# 795506519DJFLY-DG.net
KiCad netlist of a schematic drawn in Altium Designer
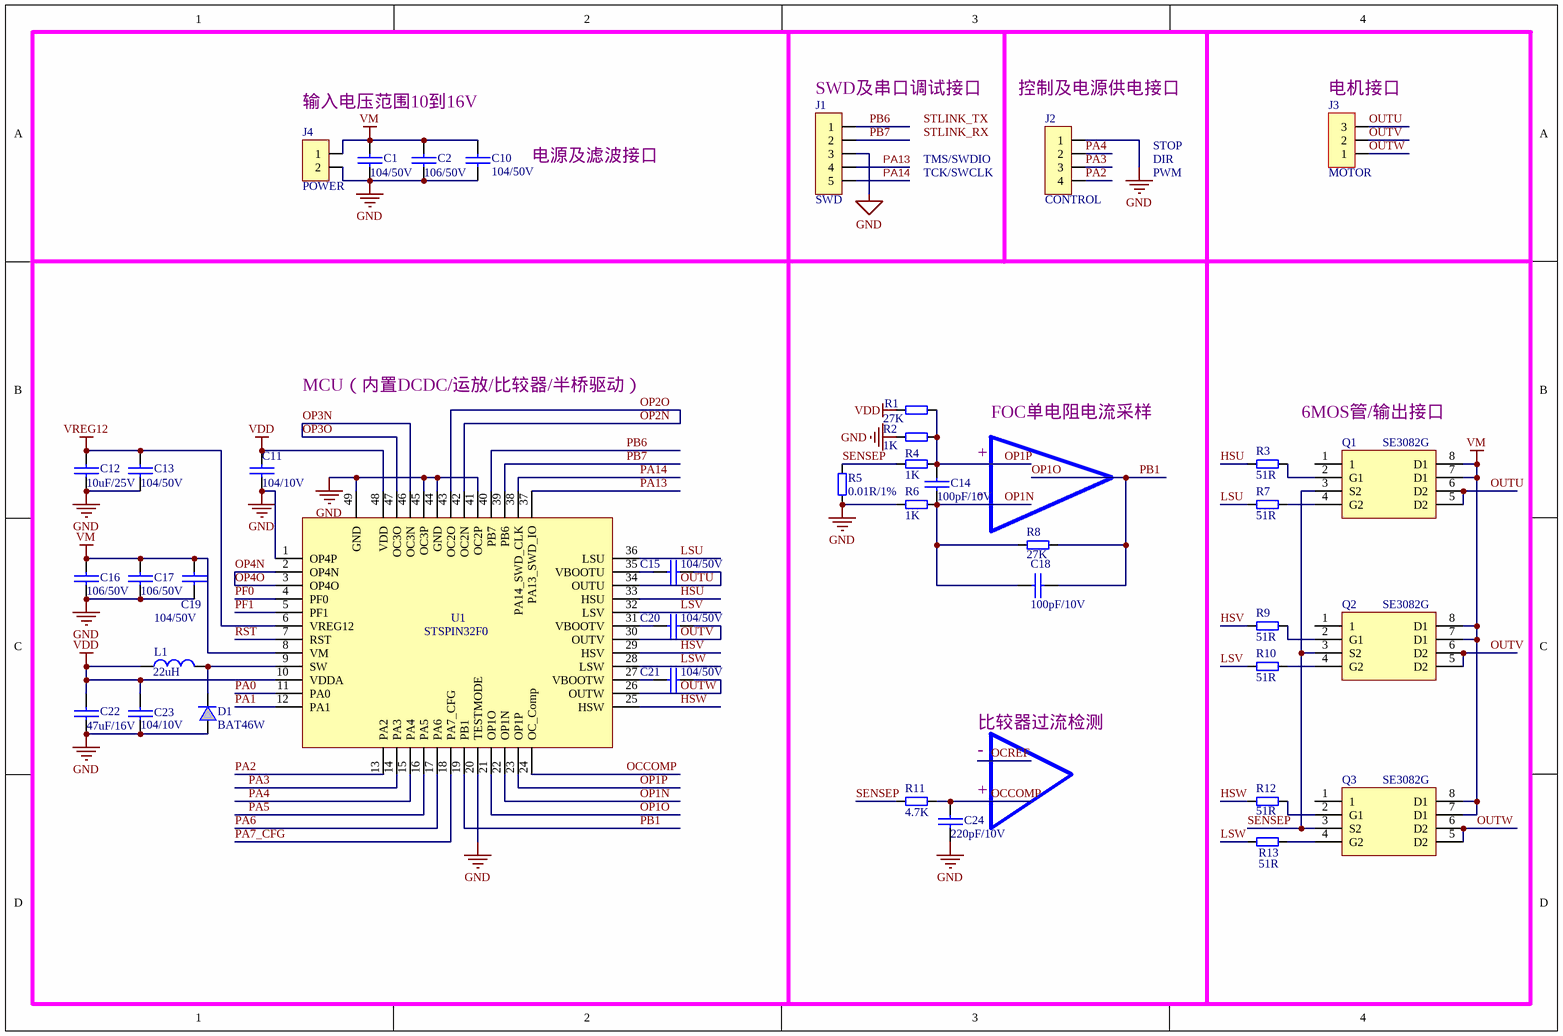
[diagram p0: 795506519DJFLY-DG.SchDoc]

(export (version "E")
  (design (tool "Eeschema 10.0.6"))
  (components
    (comp (ref "C1")
      (value "104/50V")
      (footprint "0805C")
      (description "C")
      (libsource (lib "zh") (part "C"))
    )
    (comp (ref "C2")
      (value "106/50V")
      (footprint "1206C")
      (description "C")
      (libsource (lib "zh") (part "C"))
    )
    (comp (ref "C10")
      (value "104/50V")
      (footprint "0805C")
      (description "C")
      (libsource (lib "zh") (part "C"))
    )
    (comp (ref "C11")
      (value "104/10V")
      (footprint "0603C")
      (description "C")
      (libsource (lib "zh") (part "C"))
    )
    (comp (ref "C12")
      (value "10uF/25V")
      (footprint "1206C")
      (description "C")
      (libsource (lib "zh") (part "C"))
    )
    (comp (ref "C13")
      (value "104/50V")
      (footprint "0805C")
      (description "C")
      (libsource (lib "zh") (part "C"))
    )
    (comp (ref "C14")
      (value "100pF/10V")
      (footprint "0603C")
      (description "C")
      (libsource (lib "zh") (part "C"))
    )
    (comp (ref "C15")
      (value "104/50V")
      (footprint "0805C")
      (description "C")
      (libsource (lib "zh") (part "C"))
    )
    (comp (ref "C16")
      (value "106/50V")
      (footprint "1206C")
      (description "C")
      (libsource (lib "zh") (part "C"))
    )
    (comp (ref "C17")
      (value "106/50V")
      (footprint "1206C")
      (description "C")
      (libsource (lib "zh") (part "C"))
    )
    (comp (ref "C18")
      (value "100pF/10V")
      (footprint "0603C")
      (description "C")
      (libsource (lib "zh") (part "C"))
    )
    (comp (ref "C19")
      (value "104/50V")
      (footprint "0805C")
      (description "C")
      (libsource (lib "zh") (part "C"))
    )
    (comp (ref "C20")
      (value "104/50V")
      (footprint "0805C")
      (description "C")
      (libsource (lib "zh") (part "C"))
    )
    (comp (ref "C21")
      (value "104/50V")
      (footprint "0805C")
      (description "C")
      (libsource (lib "zh") (part "C"))
    )
    (comp (ref "C22")
      (value "47uF/16V")
      (footprint "1206C")
      (description "C")
      (libsource (lib "zh") (part "C"))
    )
    (comp (ref "C23")
      (value "104/10V")
      (footprint "0603C")
      (description "C")
      (libsource (lib "zh") (part "C"))
    )
    (comp (ref "C24")
      (value "220pF/10V")
      (footprint "0603C")
      (description "C")
      (libsource (lib "zh") (part "C"))
    )
    (comp (ref "D1")
      (value "BAT46W")
      (footprint "SOD-123")
      (description "D")
      (libsource (lib "zh") (part "D"))
    )
    (comp (ref "J1") (value "SWD") (footprint "SIP5") (description "CN") (libsource (lib "zh") (part "CON5")))
    (comp (ref "J2")
      (value "CONTROL")
      (footprint "SIP4")
      (description "CN")
      (libsource (lib "zh") (part "CON4"))
    )
    (comp (ref "J3")
      (value "MOTOR")
      (footprint "POW-3.81-3S")
      (description "CN")
      (libsource (lib "zh") (part "CON3"))
    )
    (comp (ref "J4")
      (value "POWER")
      (footprint "POW-3.81-2S")
      (description "J")
      (libsource (lib "zh") (part "CON2"))
    )
    (comp (ref "L1")
      (value "22uH")
      (footprint "1812c")
      (description "10uH")
      (libsource (lib "zh1") (part "L"))
    )
    (comp (ref "Q1") (value "SE3082G") (footprint "DFN5*6") (libsource (lib "LY-SCH") (part "SE3082G")))
    (comp (ref "Q2") (value "SE3082G") (footprint "DFN5*6") (libsource (lib "LY-SCH") (part "SE3082G")))
    (comp (ref "Q3") (value "SE3082G") (footprint "DFN5*6") (libsource (lib "LY-SCH") (part "SE3082G")))
    (comp (ref "R1") (value "27K") (footprint "0603") (description "10K") (libsource (lib "zh") (part "R")))
    (comp (ref "R2") (value "1K") (footprint "0603") (description "10K") (libsource (lib "zh") (part "R")))
    (comp (ref "R3") (value "51R") (footprint "0805") (description "10K") (libsource (lib "zh1") (part "R")))
    (comp (ref "R4") (value "1K") (footprint "0603") (description "10K") (libsource (lib "zh") (part "R")))
    (comp (ref "R5")
      (value "0.01R/1%")
      (footprint "2512-K")
      (description "10K")
      (libsource (lib "zh") (part "R"))
    )
    (comp (ref "R6") (value "1K") (footprint "0603") (description "10K") (libsource (lib "zh") (part "R")))
    (comp (ref "R7") (value "51R") (footprint "0805") (description "10K") (libsource (lib "zh1") (part "R")))
    (comp (ref "R8") (value "27K") (footprint "0603") (description "10K") (libsource (lib "zh") (part "R")))
    (comp (ref "R9") (value "51R") (footprint "0805") (description "10K") (libsource (lib "zh1") (part "R")))
    (comp (ref "R10") (value "51R") (footprint "0805") (description "10K") (libsource (lib "zh1") (part "R")))
    (comp (ref "R11") (value "4.7K") (footprint "0603") (description "10K") (libsource (lib "zh") (part "R")))
    (comp (ref "R12") (value "51R") (footprint "0805") (description "10K") (libsource (lib "zh1") (part "R")))
    (comp (ref "R13") (value "51R") (footprint "0805") (description "10K") (libsource (lib "zh1") (part "R")))
    (comp (ref "U1")
      (value "STSPIN32F0")
      (footprint "VFQFPN48")
      (libsource (lib "LY-SCH") (part "STSPIN32F0"))
    )
  )
  (nets
    (net (code "1") (name "/HSU") (class "Default")
      (node (ref "R3") (pin "1") (pinfunction "1_1") (pintype "passive"))
      (node (ref "U1") (pin "33") (pinfunction "HSU_33") (pintype "passive"))
    )
    (net (code "2") (name "/HSV") (class "Default")
      (node (ref "R9") (pin "1") (pinfunction "1_1") (pintype "passive"))
      (node (ref "U1") (pin "29") (pinfunction "HSV_29") (pintype "passive"))
    )
    (net (code "3") (name "/HSW") (class "Default")
      (node (ref "R12") (pin "1") (pinfunction "1_1") (pintype "passive"))
      (node (ref "U1") (pin "25") (pinfunction "HSW_25") (pintype "passive"))
    )
    (net (code "4") (name "/LSU") (class "Default")
      (node (ref "R7") (pin "1") (pinfunction "1_1") (pintype "passive"))
      (node (ref "U1") (pin "36") (pinfunction "LSU_36") (pintype "passive"))
    )
    (net (code "5") (name "/LSV") (class "Default")
      (node (ref "R10") (pin "1") (pinfunction "1_1") (pintype "passive"))
      (node (ref "U1") (pin "32") (pinfunction "LSV_32") (pintype "passive"))
    )
    (net (code "6") (name "/LSW") (class "Default")
      (node (ref "R13") (pin "1") (pinfunction "1_1") (pintype "passive"))
      (node (ref "U1") (pin "28") (pinfunction "LSW_28") (pintype "passive"))
    )
    (net (code "7") (name "/OCCOMP") (class "Default")
      (node (ref "C24") (pin "1") (pintype "passive"))
      (node (ref "R11") (pin "1") (pinfunction "1_1") (pintype "passive"))
      (node (ref "U1") (pin "24") (pinfunction "OC_Comp_24") (pintype "passive"))
    )
    (net (code "9") (name "/OP1N") (class "Default")
      (node (ref "C14") (pin "2") (pintype "passive"))
      (node (ref "C18") (pin "1") (pintype "passive"))
      (node (ref "R6") (pin "1") (pinfunction "1_1") (pintype "passive"))
      (node (ref "R8") (pin "2") (pinfunction "2_2") (pintype "passive"))
      (node (ref "U1") (pin "22") (pinfunction "OP1N_22") (pintype "passive"))
    )
    (net (code "10") (name "/OP1O") (class "Default")
      (node (ref "C18") (pin "2") (pintype "passive"))
      (node (ref "R8") (pin "1") (pinfunction "1_1") (pintype "passive"))
      (node (ref "U1") (pin "19") (pinfunction "PB1_19") (pintype "passive"))
      (node (ref "U1") (pin "21") (pinfunction "OP1O_21") (pintype "passive"))
    )
    (net (code "11") (name "/OP1P") (class "Default")
      (node (ref "C14") (pin "1") (pintype "passive"))
      (node (ref "R1") (pin "1") (pinfunction "1_1") (pintype "passive"))
      (node (ref "R2") (pin "2") (pinfunction "2_2") (pintype "passive"))
      (node (ref "R4") (pin "1") (pinfunction "1_1") (pintype "passive"))
      (node (ref "U1") (pin "23") (pinfunction "OP1P_23") (pintype "passive"))
    )
    (net (code "12") (name "/OP2N") (class "Default")
      (node (ref "U1") (pin "42") (pinfunction "OC2N_42") (pintype "passive"))
      (node (ref "U1") (pin "43") (pinfunction "OC2O_43") (pintype "passive"))
    )
    (net (code "13") (name "/OP3N") (class "Default")
      (node (ref "U1") (pin "46") (pinfunction "OC3N_46") (pintype "passive"))
      (node (ref "U1") (pin "47") (pinfunction "OC3O_47") (pintype "passive"))
    )
    (net (code "14") (name "/OP4N") (class "Default")
      (node (ref "U1") (pin "2") (pinfunction "OP4N_2") (pintype "passive"))
      (node (ref "U1") (pin "3") (pinfunction "OP4O_3") (pintype "passive"))
    )
    (net (code "15") (name "/OUTU") (class "Default")
      (node (ref "C15") (pin "2") (pintype "passive"))
      (node (ref "J3") (pin "3") (pinfunction "3_3") (pintype "passive"))
      (node (ref "Q1") (pin "5") (pinfunction "D2_5") (pintype "passive"))
      (node (ref "Q1") (pin "6") (pinfunction "D2_6") (pintype "passive"))
      (node (ref "U1") (pin "34") (pinfunction "OUTU_34") (pintype "passive"))
    )
    (net (code "16") (name "/OUTV") (class "Default")
      (node (ref "C20") (pin "2") (pintype "passive"))
      (node (ref "J3") (pin "2") (pinfunction "2_2") (pintype "passive"))
      (node (ref "Q2") (pin "5") (pinfunction "D2_5") (pintype "passive"))
      (node (ref "Q2") (pin "6") (pinfunction "D2_6") (pintype "passive"))
      (node (ref "U1") (pin "30") (pinfunction "OUTV_30") (pintype "passive"))
    )
    (net (code "17") (name "/OUTW") (class "Default")
      (node (ref "C21") (pin "2") (pintype "passive"))
      (node (ref "J3") (pin "1") (pinfunction "1_1") (pintype "passive"))
      (node (ref "Q3") (pin "5") (pinfunction "D2_5") (pintype "passive"))
      (node (ref "Q3") (pin "6") (pinfunction "D2_6") (pintype "passive"))
      (node (ref "U1") (pin "26") (pinfunction "OUTW_26") (pintype "passive"))
    )
    (net (code "18") (name "/PA0") (class "Default")
      (node (ref "U1") (pin "11") (pinfunction "PA0_11") (pintype "passive"))
    )
    (net (code "19") (name "/PA1") (class "Default")
      (node (ref "U1") (pin "12") (pinfunction "PA1_12") (pintype "passive"))
    )
    (net (code "20") (name "/PA2") (class "Default")
      (node (ref "J2") (pin "4") (pinfunction "4_4") (pintype "passive"))
      (node (ref "U1") (pin "13") (pinfunction "PA2_13") (pintype "passive"))
    )
    (net (code "21") (name "/PA3") (class "Default")
      (node (ref "J2") (pin "3") (pinfunction "3_3") (pintype "passive"))
      (node (ref "U1") (pin "14") (pinfunction "PA3_14") (pintype "passive"))
    )
    (net (code "22") (name "/PA4") (class "Default")
      (node (ref "J2") (pin "2") (pinfunction "2_2") (pintype "passive"))
      (node (ref "U1") (pin "15") (pinfunction "PA4_15") (pintype "passive"))
    )
    (net (code "23") (name "/PA5") (class "Default")
      (node (ref "U1") (pin "16") (pinfunction "PA5_16") (pintype "passive"))
    )
    (net (code "24") (name "/PA6") (class "Default")
      (node (ref "U1") (pin "17") (pinfunction "PA6_17") (pintype "passive"))
    )
    (net (code "25") (name "/PA7_CFG") (class "Default")
      (node (ref "U1") (pin "18") (pinfunction "PA7_CFG_18") (pintype "passive"))
    )
    (net (code "26") (name "/PA13") (class "Default")
      (node (ref "J1") (pin "4") (pinfunction "4_4") (pintype "passive"))
      (node (ref "U1") (pin "37") (pinfunction "PA13_SWD_IO_37") (pintype "passive"))
    )
    (net (code "27") (name "/PA14") (class "Default")
      (node (ref "J1") (pin "5") (pinfunction "5_5") (pintype "passive"))
      (node (ref "U1") (pin "38") (pinfunction "PA14_SWD_CLK_38") (pintype "passive"))
    )
    (net (code "28") (name "/PB6") (class "Default")
      (node (ref "J1") (pin "1") (pinfunction "1_1") (pintype "passive"))
      (node (ref "U1") (pin "40") (pinfunction "PB7_40") (pintype "passive"))
    )
    (net (code "29") (name "/PB7") (class "Default")
      (node (ref "J1") (pin "2") (pinfunction "2_2") (pintype "passive"))
      (node (ref "U1") (pin "39") (pinfunction "PB6_39") (pintype "passive"))
    )
    (net (code "30") (name "/PF0") (class "Default")
      (node (ref "U1") (pin "4") (pinfunction "PF0_4") (pintype "passive"))
    )
    (net (code "31") (name "/PF1") (class "Default")
      (node (ref "U1") (pin "5") (pinfunction "PF1_5") (pintype "passive"))
    )
    (net (code "32") (name "/RST") (class "Default")
      (node (ref "U1") (pin "7") (pinfunction "RST_7") (pintype "passive"))
    )
    (net (code "33") (name "/SENSEP") (class "Default")
      (node (ref "Q1") (pin "3") (pinfunction "S2_3") (pintype "passive"))
      (node (ref "Q2") (pin "3") (pinfunction "S2_3") (pintype "passive"))
      (node (ref "Q3") (pin "3") (pinfunction "S2_3") (pintype "passive"))
      (node (ref "R11") (pin "2") (pinfunction "2_2") (pintype "passive"))
      (node (ref "R4") (pin "2") (pinfunction "2_2") (pintype "passive"))
      (node (ref "R5") (pin "1") (pinfunction "1_1") (pintype "passive"))
    )
    (net (code "36") (name "GND") (class "Default")
      (node (ref "C1") (pin "2") (pintype "passive"))
      (node (ref "C10") (pin "2") (pintype "passive"))
      (node (ref "C11") (pin "2") (pintype "passive"))
      (node (ref "C12") (pin "2") (pintype "passive"))
      (node (ref "C13") (pin "2") (pintype "passive"))
      (node (ref "C16") (pin "2") (pintype "passive"))
      (node (ref "C17") (pin "2") (pintype "passive"))
      (node (ref "C19") (pin "2") (pintype "passive"))
      (node (ref "C2") (pin "2") (pintype "passive"))
      (node (ref "C22") (pin "2") (pintype "passive"))
      (node (ref "C23") (pin "2") (pintype "passive"))
      (node (ref "C24") (pin "2") (pintype "passive"))
      (node (ref "D1") (pin "A") (pinfunction "1_A") (pintype "passive"))
      (node (ref "J1") (pin "3") (pinfunction "3_3") (pintype "passive"))
      (node (ref "J2") (pin "1") (pinfunction "1_1") (pintype "passive"))
      (node (ref "J4") (pin "2") (pinfunction "2_2") (pintype "passive"))
      (node (ref "R2") (pin "1") (pinfunction "1_1") (pintype "passive"))
      (node (ref "R5") (pin "2") (pinfunction "2_2") (pintype "passive"))
      (node (ref "R6") (pin "2") (pinfunction "2_2") (pintype "passive"))
      (node (ref "U1") (pin "1") (pinfunction "OP4P_1") (pintype "passive"))
      (node (ref "U1") (pin "20") (pinfunction "TESTMODE_20") (pintype "passive"))
      (node (ref "U1") (pin "41") (pinfunction "OC2P_41") (pintype "passive"))
      (node (ref "U1") (pin "44") (pinfunction "GND_44") (pintype "passive"))
      (node (ref "U1") (pin "45") (pinfunction "OC3P_45") (pintype "passive"))
      (node (ref "U1") (pin "49") (pinfunction "GND_49") (pintype "passive"))
    )
    (net (code "37") (name "Net-(D1-2)") (class "Default")
      (node (ref "D1") (pin "K") (pinfunction "2_K") (pintype "passive"))
      (node (ref "L1") (pin "2") (pinfunction "2_2") (pintype "passive"))
      (node (ref "U1") (pin "9") (pinfunction "SW_9") (pintype "passive"))
    )
    (net (code "38") (name "Net-(Q1-G1)") (class "Default")
      (node (ref "Q1") (pin "2") (pinfunction "G1_2") (pintype "passive"))
      (node (ref "R3") (pin "2") (pinfunction "2_2") (pintype "passive"))
    )
    (net (code "39") (name "Net-(Q1-G2)") (class "Default")
      (node (ref "Q1") (pin "4") (pinfunction "G2_4") (pintype "passive"))
      (node (ref "R7") (pin "2") (pinfunction "2_2") (pintype "passive"))
    )
    (net (code "40") (name "Net-(Q2-G1)") (class "Default")
      (node (ref "Q2") (pin "2") (pinfunction "G1_2") (pintype "passive"))
      (node (ref "R9") (pin "2") (pinfunction "2_2") (pintype "passive"))
    )
    (net (code "41") (name "Net-(Q2-G2)") (class "Default")
      (node (ref "Q2") (pin "4") (pinfunction "G2_4") (pintype "passive"))
      (node (ref "R10") (pin "2") (pinfunction "2_2") (pintype "passive"))
    )
    (net (code "42") (name "Net-(Q3-G1)") (class "Default")
      (node (ref "Q3") (pin "2") (pinfunction "G1_2") (pintype "passive"))
      (node (ref "R12") (pin "2") (pinfunction "2_2") (pintype "passive"))
    )
    (net (code "43") (name "Net-(Q3-G2)") (class "Default")
      (node (ref "Q3") (pin "4") (pinfunction "G2_4") (pintype "passive"))
      (node (ref "R13") (pin "2") (pinfunction "2_2") (pintype "passive"))
    )
    (net (code "44") (name "Net-(U1-VBOOTU)") (class "Default")
      (node (ref "C15") (pin "1") (pintype "passive"))
      (node (ref "U1") (pin "35") (pinfunction "VBOOTU_35") (pintype "passive"))
    )
    (net (code "45") (name "Net-(U1-VBOOTV)") (class "Default")
      (node (ref "C20") (pin "1") (pintype "passive"))
      (node (ref "U1") (pin "31") (pinfunction "VBOOTV_31") (pintype "passive"))
    )
    (net (code "46") (name "Net-(U1-VBOOTW)") (class "Default")
      (node (ref "C21") (pin "1") (pintype "passive"))
      (node (ref "U1") (pin "27") (pinfunction "VBOOTW_27") (pintype "passive"))
    )
    (net (code "47") (name "VDD") (class "Default")
      (node (ref "C11") (pin "1") (pintype "passive"))
      (node (ref "C22") (pin "1") (pintype "passive"))
      (node (ref "C23") (pin "1") (pintype "passive"))
      (node (ref "L1") (pin "1") (pinfunction "1_1") (pintype "passive"))
      (node (ref "R1") (pin "2") (pinfunction "2_2") (pintype "passive"))
      (node (ref "U1") (pin "10") (pinfunction "VDDA_10") (pintype "passive"))
      (node (ref "U1") (pin "48") (pinfunction "VDD_48") (pintype "passive"))
    )
    (net (code "48") (name "VM") (class "Default")
      (node (ref "C1") (pin "1") (pintype "passive"))
      (node (ref "C10") (pin "1") (pintype "passive"))
      (node (ref "C16") (pin "1") (pintype "passive"))
      (node (ref "C17") (pin "1") (pintype "passive"))
      (node (ref "C19") (pin "1") (pintype "passive"))
      (node (ref "C2") (pin "1") (pintype "passive"))
      (node (ref "J4") (pin "1") (pinfunction "1_1") (pintype "passive"))
      (node (ref "Q1") (pin "7") (pinfunction "D1_7") (pintype "passive"))
      (node (ref "Q1") (pin "8") (pinfunction "D1_8") (pintype "passive"))
      (node (ref "Q2") (pin "7") (pinfunction "D1_7") (pintype "passive"))
      (node (ref "Q2") (pin "8") (pinfunction "D1_8") (pintype "passive"))
      (node (ref "Q3") (pin "7") (pinfunction "D1_7") (pintype "passive"))
      (node (ref "Q3") (pin "8") (pinfunction "D1_8") (pintype "passive"))
      (node (ref "U1") (pin "8") (pinfunction "VM_8") (pintype "passive"))
    )
    (net (code "49") (name "VREG12") (class "Default")
      (node (ref "C12") (pin "1") (pintype "passive"))
      (node (ref "C13") (pin "1") (pintype "passive"))
      (node (ref "U1") (pin "6") (pinfunction "VREG12_6") (pintype "passive"))
    )
    (net (code "50") (name "unconnected-(Q1-Pad1)") (class "Default")
      (node (ref "Q1") (pin "1") (pinfunction "1_1") (pintype "passive"))
    )
    (net (code "51") (name "unconnected-(Q2-Pad1)") (class "Default")
      (node (ref "Q2") (pin "1") (pinfunction "1_1") (pintype "passive"))
    )
    (net (code "52") (name "unconnected-(Q3-Pad1)") (class "Default")
      (node (ref "Q3") (pin "1") (pinfunction "1_1") (pintype "passive"))
    )
  )
)
